# SHDN-BSPD-S02-V00-BSPDSystem.net
KiCad netlist of a schematic drawn in Altium Designer
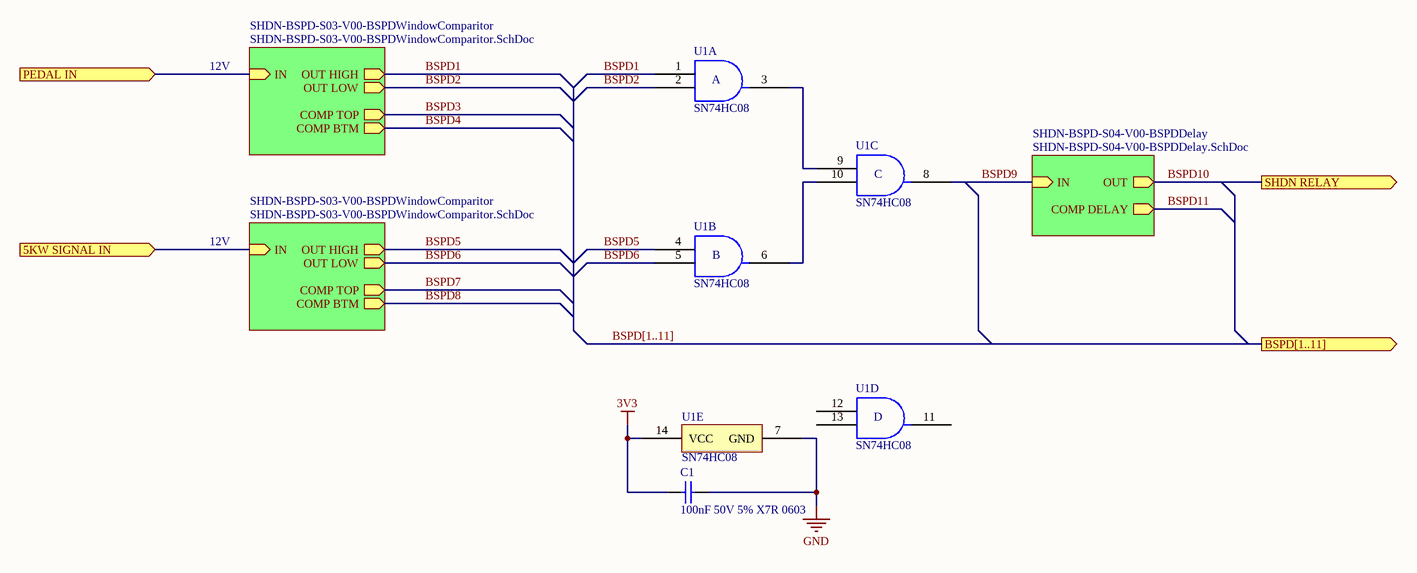
[diagram p0: SHDN-BSPD-S02-V00-BSPDSystem.SchDoc]

(export (version "E")
  (design (tool "Eeschema 10.0.6"))
  (components
    (comp (ref "C1")
      (value "100nF 50V 5% X7R 0603")
      (footprint "Cap_Ceramic_0603")
      (description "Capacitor, Ceramic, SMD, 100nF, 50V, 5%, X7R, 0603")
      (libsource (lib "StandardCapacitors") (part "100nF 50V 5% X7R 0603"))
    )
    (comp (ref "U1")
      (value "SN74HC08")
      (footprint "TSSOP-14")
      (description "Quadruple 2-Input Positive-AND Gates")
      (libsource (lib "QUTMS_OpAmpLibrary") (part "SN74HC08"))
    )
  )
  (nets
    (net (code "2") (name "/BSPD1") (class "Default")
      (node (ref "U1") (pin "1") (pinfunction "1A_1") (pintype "passive"))
    )
    (net (code "3") (name "/BSPD2") (class "Default")
      (node (ref "U1") (pin "2") (pinfunction "1B_2") (pintype "passive"))
    )
    (net (code "6") (name "/BSPD5") (class "Default")
      (node (ref "U1") (pin "4") (pinfunction "2A_4") (pintype "passive"))
    )
    (net (code "7") (name "/BSPD6") (class "Default")
      (node (ref "U1") (pin "5") (pinfunction "2B_5") (pintype "passive"))
    )
    (net (code "10") (name "/BSPD9") (class "Default")
      (node (ref "U1") (pin "8") (pinfunction "3Y_8") (pintype "passive"))
    )
    (net (code "15") (name "3V3") (class "Default")
      (node (ref "C1") (pin "2") (pinfunction "2_2") (pintype "passive"))
      (node (ref "U1") (pin "14") (pinfunction "VCC_14") (pintype "passive"))
    )
    (net (code "16") (name "GND") (class "Default")
      (node (ref "C1") (pin "1") (pinfunction "1_1") (pintype "passive"))
      (node (ref "U1") (pin "7") (pinfunction "GND_7") (pintype "passive"))
    )
    (net (code "17") (name "Net-(U1A-1Y)") (class "Default")
      (node (ref "U1") (pin "3") (pinfunction "1Y_3") (pintype "passive"))
      (node (ref "U1") (pin "9") (pinfunction "3A_9") (pintype "passive"))
    )
    (net (code "18") (name "Net-(U1B-2Y)") (class "Default")
      (node (ref "U1") (pin "10") (pinfunction "3B_10") (pintype "passive"))
      (node (ref "U1") (pin "6") (pinfunction "2Y_6") (pintype "passive"))
    )
    (net (code "19") (name "unconnected-(U1D-4A-Pad12)") (class "Default")
      (node (ref "U1") (pin "12") (pinfunction "4A_12") (pintype "passive"))
    )
    (net (code "20") (name "unconnected-(U1D-4B-Pad13)") (class "Default")
      (node (ref "U1") (pin "13") (pinfunction "4B_13") (pintype "passive"))
    )
    (net (code "21") (name "unconnected-(U1D-4Y-Pad11)") (class "Default")
      (node (ref "U1") (pin "11") (pinfunction "4Y_11") (pintype "passive"))
    )
  )
)
